# rw-linear-20mm-mk-1_0_0.net
KiCad netlist of a schematic drawn in EAGLE
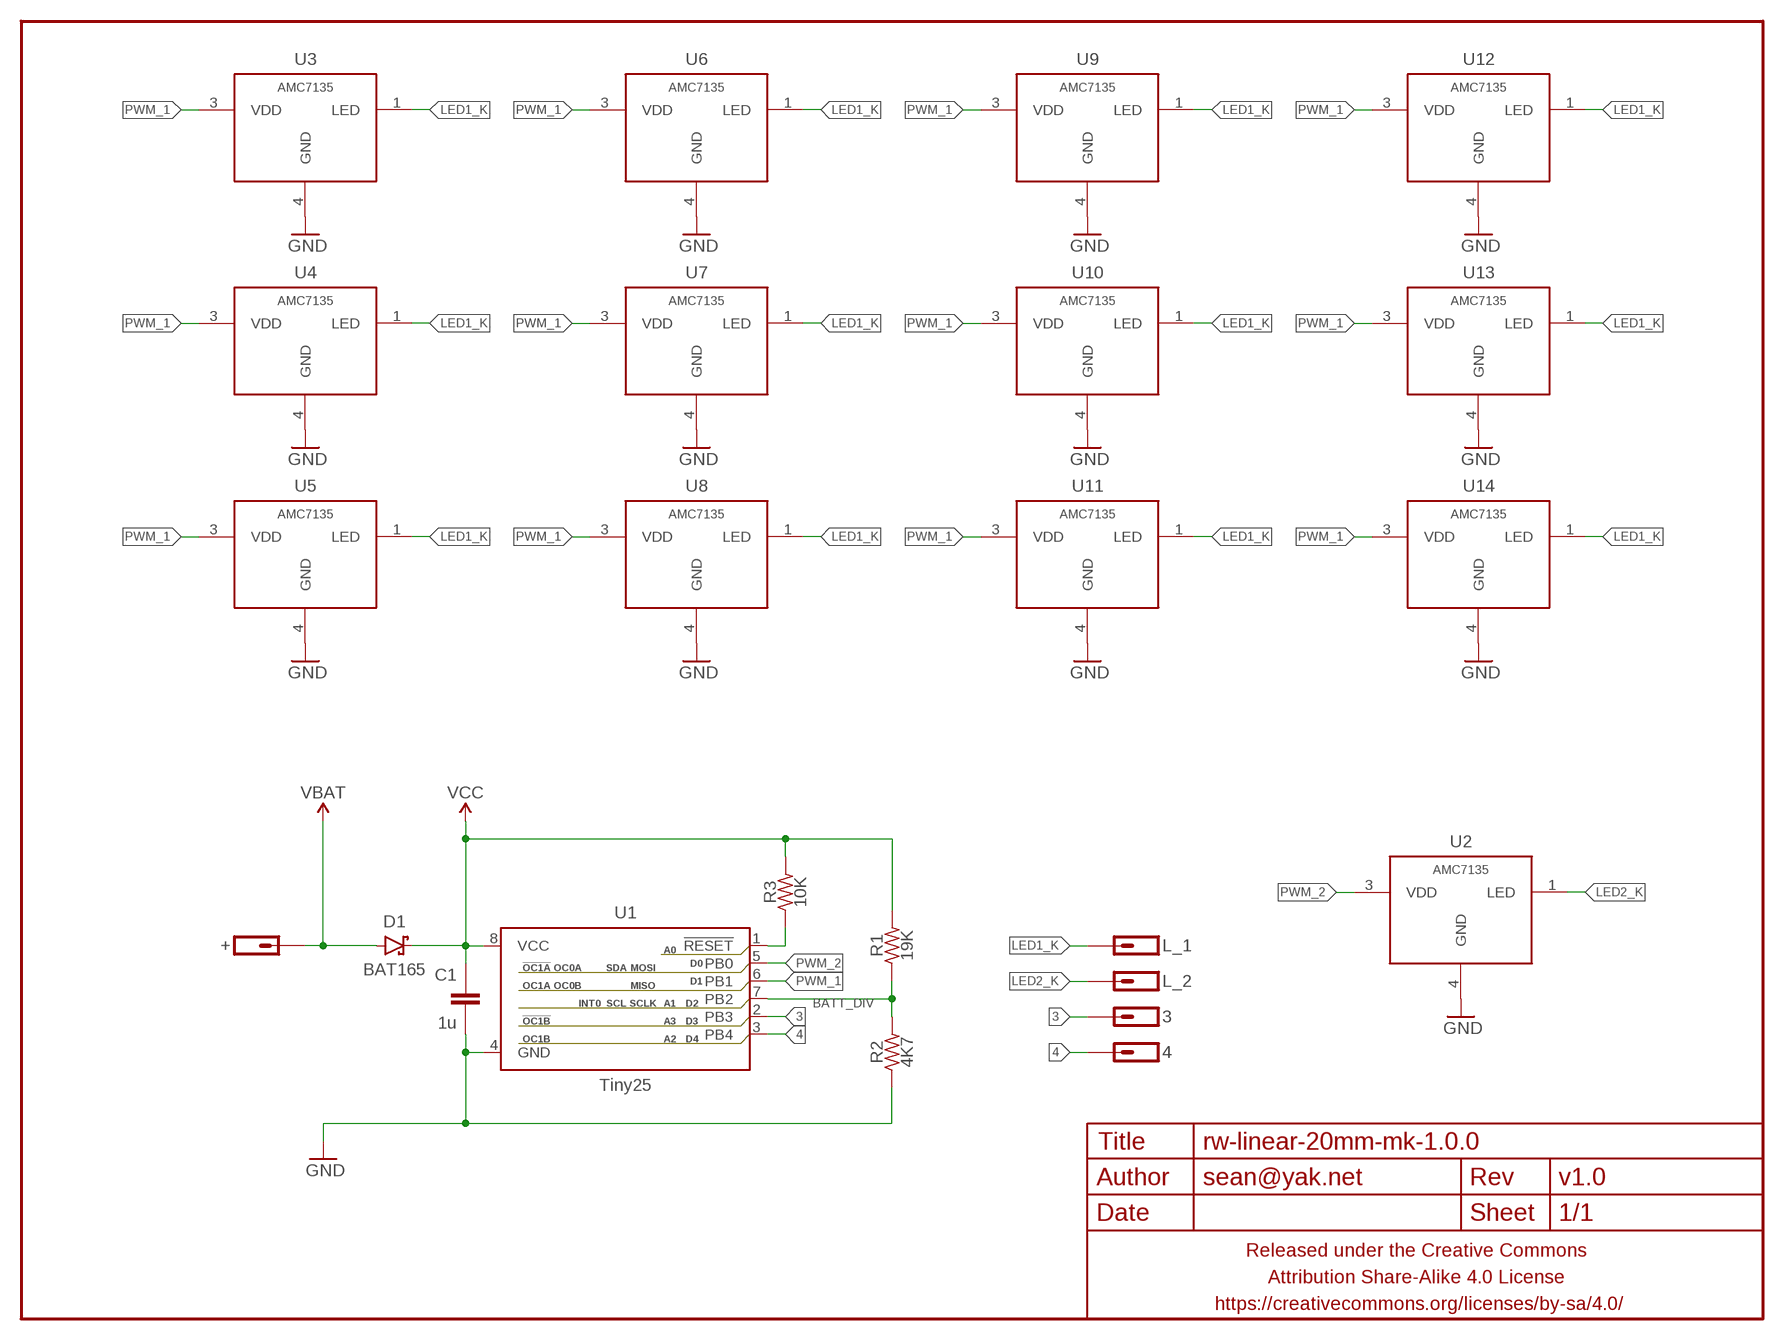
[diagram p0: schematic, sheet 1]

(export (version "E")
  (design (tool "Eeschema 10.0.6"))
  (components
    (comp (ref "+")
      (value "M01PTH-1MM-CIR-NS")
      (footprint "eagle-import:1X01-1MM-CIR-NS")
      (libsource (lib "eagle-import") (part "M01PTH-1MM-CIR-NS"))
    )
    (comp (ref "3")
      (value "M01SMD-1MM-DIA-NS")
      (footprint "eagle-import:1X01-SMD-1MM-DIA-NS")
      (libsource (lib "eagle-import") (part "M01SMD-1MM-DIA-NS"))
    )
    (comp (ref "4")
      (value "M01SMD-1MM-DIA-NS")
      (footprint "eagle-import:1X01-SMD-1MM-DIA-NS")
      (libsource (lib "eagle-import") (part "M01SMD-1MM-DIA-NS"))
    )
    (comp (ref "C1")
      (value "1u")
      (footprint "eagle-import:C0603-TIGHTER")
      (libsource (lib "eagle-import") (part "CAPACITOR-CERAMICC0603-TIGHTER"))
    )
    (comp (ref "D1")
      (value "BAT165")
      (footprint "eagle-import:SMA-DIODE-SCHOTTKY")
      (libsource (lib "eagle-import") (part "DIODE-SCHOTTKYSMA"))
    )
    (comp (ref "FRAME1")
      (value "FRAME-LETTERNO_PACKAGE")
      (footprint "eagle-import:DUMMY")
      (fields (field (name "DESIGNER") "sean@yak.net") (field (name "VERSION") "v1.0"))
      (libsource (lib "eagle-import") (part "FRAME-LETTERNO_PACKAGE"))
    )
    (comp (ref "L_1")
      (value "M011X01-0.9MM-CIR")
      (footprint "eagle-import:1X01-0.9MM-CIR")
      (libsource (lib "eagle-import") (part "M011X01-0.9MM-CIR"))
    )
    (comp (ref "L_2")
      (value "M01PTH-0.8MM-CIR")
      (footprint "eagle-import:1X01-0.8MM-CIR")
      (libsource (lib "eagle-import") (part "M01PTH-0.8MM-CIR"))
    )
    (comp (ref "R1")
      (value "19K")
      (footprint "eagle-import:R0603-TIGHTER")
      (libsource (lib "eagle-import") (part "RESISTORR0603-TIGHTER"))
    )
    (comp (ref "R2")
      (value "4K7")
      (footprint "eagle-import:R0603-TIGHTER")
      (libsource (lib "eagle-import") (part "RESISTORR0603-TIGHTER"))
    )
    (comp (ref "R3")
      (value "10K")
      (footprint "eagle-import:R0603-TIGHTER")
      (libsource (lib "eagle-import") (part "RESISTORR0603-TIGHTER"))
    )
    (comp (ref "U1")
      (value "Tiny25")
      (footprint "eagle-import:SO08-NARROWER")
      (libsource (lib "eagle-import") (part "ATTINY13SOIC-NARROWPADS"))
    )
    (comp (ref "U2")
      (value "AMC7135")
      (footprint "eagle-import:SOT89-NOTHERM-ROUNDED-LESS")
      (libsource (lib "eagle-import") (part "AMC7135SOT-89-NOTHERM-ROUNDED-LESS"))
    )
    (comp (ref "U3")
      (value "AMC7135")
      (footprint "eagle-import:SOT89-NOTHERM-ROUNDED-LESS")
      (libsource (lib "eagle-import") (part "AMC7135SOT-89-NOTHERM-ROUNDED-LESS"))
    )
    (comp (ref "U4")
      (value "AMC7135")
      (footprint "eagle-import:SOT89-NOTHERM-ROUNDED-LESS")
      (libsource (lib "eagle-import") (part "AMC7135SOT-89-NOTHERM-ROUNDED-LESS"))
    )
    (comp (ref "U5")
      (value "AMC7135")
      (footprint "eagle-import:SOT89-NOTHERM-ROUNDED-LESS")
      (libsource (lib "eagle-import") (part "AMC7135SOT-89-NOTHERM-ROUNDED-LESS"))
    )
    (comp (ref "U6")
      (value "AMC7135")
      (footprint "eagle-import:SOT89-NOTHERM-ROUNDED-LESS")
      (libsource (lib "eagle-import") (part "AMC7135SOT-89-NOTHERM-ROUNDED-LESS"))
    )
    (comp (ref "U7")
      (value "AMC7135")
      (footprint "eagle-import:SOT89-NOTHERM-ROUNDED-LESS")
      (libsource (lib "eagle-import") (part "AMC7135SOT-89-NOTHERM-ROUNDED-LESS"))
    )
    (comp (ref "U8")
      (value "AMC7135")
      (footprint "eagle-import:SOT89-NOTHERM-ROUNDED-LESS")
      (libsource (lib "eagle-import") (part "AMC7135SOT-89-NOTHERM-ROUNDED-LESS"))
    )
    (comp (ref "U9")
      (value "AMC7135")
      (footprint "eagle-import:SOT89-NOTHERM-ROUNDED-LESS")
      (libsource (lib "eagle-import") (part "AMC7135SOT-89-NOTHERM-ROUNDED-LESS"))
    )
    (comp (ref "U10")
      (value "AMC7135")
      (footprint "eagle-import:SOT89-NOTHERM-ROUNDED-LESS")
      (libsource (lib "eagle-import") (part "AMC7135SOT-89-NOTHERM-ROUNDED-LESS"))
    )
    (comp (ref "U11")
      (value "AMC7135")
      (footprint "eagle-import:SOT89-NOTHERM-ROUNDED-LESS")
      (libsource (lib "eagle-import") (part "AMC7135SOT-89-NOTHERM-ROUNDED-LESS"))
    )
    (comp (ref "U12")
      (value "AMC7135")
      (footprint "eagle-import:SOT89-NOTHERM-ROUNDED-LESS")
      (libsource (lib "eagle-import") (part "AMC7135SOT-89-NOTHERM-ROUNDED-LESS"))
    )
    (comp (ref "U13")
      (value "AMC7135")
      (footprint "eagle-import:SOT89-NOTHERM-ROUNDED-LESS")
      (libsource (lib "eagle-import") (part "AMC7135SOT-89-NOTHERM-ROUNDED-LESS"))
    )
    (comp (ref "U14")
      (value "AMC7135")
      (footprint "eagle-import:SOT89-NOTHERM-ROUNDED-LESS")
      (libsource (lib "eagle-import") (part "AMC7135SOT-89-NOTHERM-ROUNDED-LESS"))
    )
  )
  (nets
    (net (code "1") (name "/BATT_DIV") (class "Default")
      (node (ref "R1") (pin "1") (pinfunction "1_1") (pintype "passive"))
      (node (ref "R2") (pin "2") (pinfunction "2_2") (pintype "passive"))
      (node (ref "U1") (pin "7") (pinfunction "PB2_7") (pintype "bidirectional"))
    )
    (net (code "2") (name "3") (class "Default")
      (node (ref "3") (pin "P$1") (pinfunction "1_P$1") (pintype "passive"))
      (node (ref "U1") (pin "2") (pinfunction "PB3_2") (pintype "bidirectional"))
    )
    (net (code "3") (name "4") (class "Default")
      (node (ref "4") (pin "P$1") (pinfunction "1_P$1") (pintype "passive"))
      (node (ref "U1") (pin "3") (pinfunction "PB4_3") (pintype "bidirectional"))
    )
    (net (code "4") (name "GND") (class "Default")
      (node (ref "C1") (pin "2") (pinfunction "2_2") (pintype "passive"))
      (node (ref "R2") (pin "1") (pinfunction "1_1") (pintype "passive"))
      (node (ref "U1") (pin "4") (pinfunction "GND_4") (pintype "bidirectional"))
      (node (ref "U10") (pin "4") (pinfunction "GND_4") (pintype "bidirectional"))
      (node (ref "U11") (pin "4") (pinfunction "GND_4") (pintype "bidirectional"))
      (node (ref "U12") (pin "4") (pinfunction "GND_4") (pintype "bidirectional"))
      (node (ref "U13") (pin "4") (pinfunction "GND_4") (pintype "bidirectional"))
      (node (ref "U14") (pin "4") (pinfunction "GND_4") (pintype "bidirectional"))
      (node (ref "U2") (pin "4") (pinfunction "GND_4") (pintype "bidirectional"))
      (node (ref "U3") (pin "4") (pinfunction "GND_4") (pintype "bidirectional"))
      (node (ref "U4") (pin "4") (pinfunction "GND_4") (pintype "bidirectional"))
      (node (ref "U5") (pin "4") (pinfunction "GND_4") (pintype "bidirectional"))
      (node (ref "U6") (pin "4") (pinfunction "GND_4") (pintype "bidirectional"))
      (node (ref "U7") (pin "4") (pinfunction "GND_4") (pintype "bidirectional"))
      (node (ref "U8") (pin "4") (pinfunction "GND_4") (pintype "bidirectional"))
      (node (ref "U9") (pin "4") (pinfunction "GND_4") (pintype "bidirectional"))
    )
    (net (code "5") (name "LED1_K") (class "Default")
      (node (ref "L_1") (pin "P$1") (pinfunction "1_P$1") (pintype "passive"))
      (node (ref "U10") (pin "1") (pinfunction "LED_1") (pintype "bidirectional"))
      (node (ref "U11") (pin "1") (pinfunction "LED_1") (pintype "bidirectional"))
      (node (ref "U12") (pin "1") (pinfunction "LED_1") (pintype "bidirectional"))
      (node (ref "U13") (pin "1") (pinfunction "LED_1") (pintype "bidirectional"))
      (node (ref "U14") (pin "1") (pinfunction "LED_1") (pintype "bidirectional"))
      (node (ref "U3") (pin "1") (pinfunction "LED_1") (pintype "bidirectional"))
      (node (ref "U4") (pin "1") (pinfunction "LED_1") (pintype "bidirectional"))
      (node (ref "U5") (pin "1") (pinfunction "LED_1") (pintype "bidirectional"))
      (node (ref "U6") (pin "1") (pinfunction "LED_1") (pintype "bidirectional"))
      (node (ref "U7") (pin "1") (pinfunction "LED_1") (pintype "bidirectional"))
      (node (ref "U8") (pin "1") (pinfunction "LED_1") (pintype "bidirectional"))
      (node (ref "U9") (pin "1") (pinfunction "LED_1") (pintype "bidirectional"))
    )
    (net (code "6") (name "LED2_K") (class "Default")
      (node (ref "L_2") (pin "1") (pinfunction "1_1") (pintype "passive"))
      (node (ref "U2") (pin "1") (pinfunction "LED_1") (pintype "bidirectional"))
    )
    (net (code "7") (name "Net-(U1-~{RESET})") (class "Default")
      (node (ref "R3") (pin "1") (pinfunction "1_1") (pintype "passive"))
      (node (ref "U1") (pin "1") (pinfunction "~{RESET}_1") (pintype "bidirectional"))
    )
    (net (code "8") (name "PWM_1") (class "Default")
      (node (ref "U1") (pin "6") (pinfunction "PB1_6") (pintype "bidirectional"))
      (node (ref "U10") (pin "3") (pinfunction "VDD_3") (pintype "bidirectional"))
      (node (ref "U11") (pin "3") (pinfunction "VDD_3") (pintype "bidirectional"))
      (node (ref "U12") (pin "3") (pinfunction "VDD_3") (pintype "bidirectional"))
      (node (ref "U13") (pin "3") (pinfunction "VDD_3") (pintype "bidirectional"))
      (node (ref "U14") (pin "3") (pinfunction "VDD_3") (pintype "bidirectional"))
      (node (ref "U3") (pin "3") (pinfunction "VDD_3") (pintype "bidirectional"))
      (node (ref "U4") (pin "3") (pinfunction "VDD_3") (pintype "bidirectional"))
      (node (ref "U5") (pin "3") (pinfunction "VDD_3") (pintype "bidirectional"))
      (node (ref "U6") (pin "3") (pinfunction "VDD_3") (pintype "bidirectional"))
      (node (ref "U7") (pin "3") (pinfunction "VDD_3") (pintype "bidirectional"))
      (node (ref "U8") (pin "3") (pinfunction "VDD_3") (pintype "bidirectional"))
      (node (ref "U9") (pin "3") (pinfunction "VDD_3") (pintype "bidirectional"))
    )
    (net (code "9") (name "PWM_2") (class "Default")
      (node (ref "U1") (pin "5") (pinfunction "PB0_5") (pintype "bidirectional"))
      (node (ref "U2") (pin "3") (pinfunction "VDD_3") (pintype "bidirectional"))
    )
    (net (code "10") (name "VBAT") (class "Default")
      (node (ref "+") (pin "1") (pinfunction "1_1") (pintype "passive"))
      (node (ref "D1") (pin "A") (pinfunction "A_A") (pintype "passive"))
    )
    (net (code "11") (name "VCC") (class "Default")
      (node (ref "C1") (pin "1") (pinfunction "1_1") (pintype "passive"))
      (node (ref "D1") (pin "C") (pinfunction "C_C") (pintype "passive"))
      (node (ref "R1") (pin "2") (pinfunction "2_2") (pintype "passive"))
      (node (ref "R3") (pin "2") (pinfunction "2_2") (pintype "passive"))
      (node (ref "U1") (pin "8") (pinfunction "VCC_8") (pintype "bidirectional"))
    )
  )
)
